# ble-jig-v1_1_-_respin.net
KiCad netlist of a schematic drawn in EAGLE
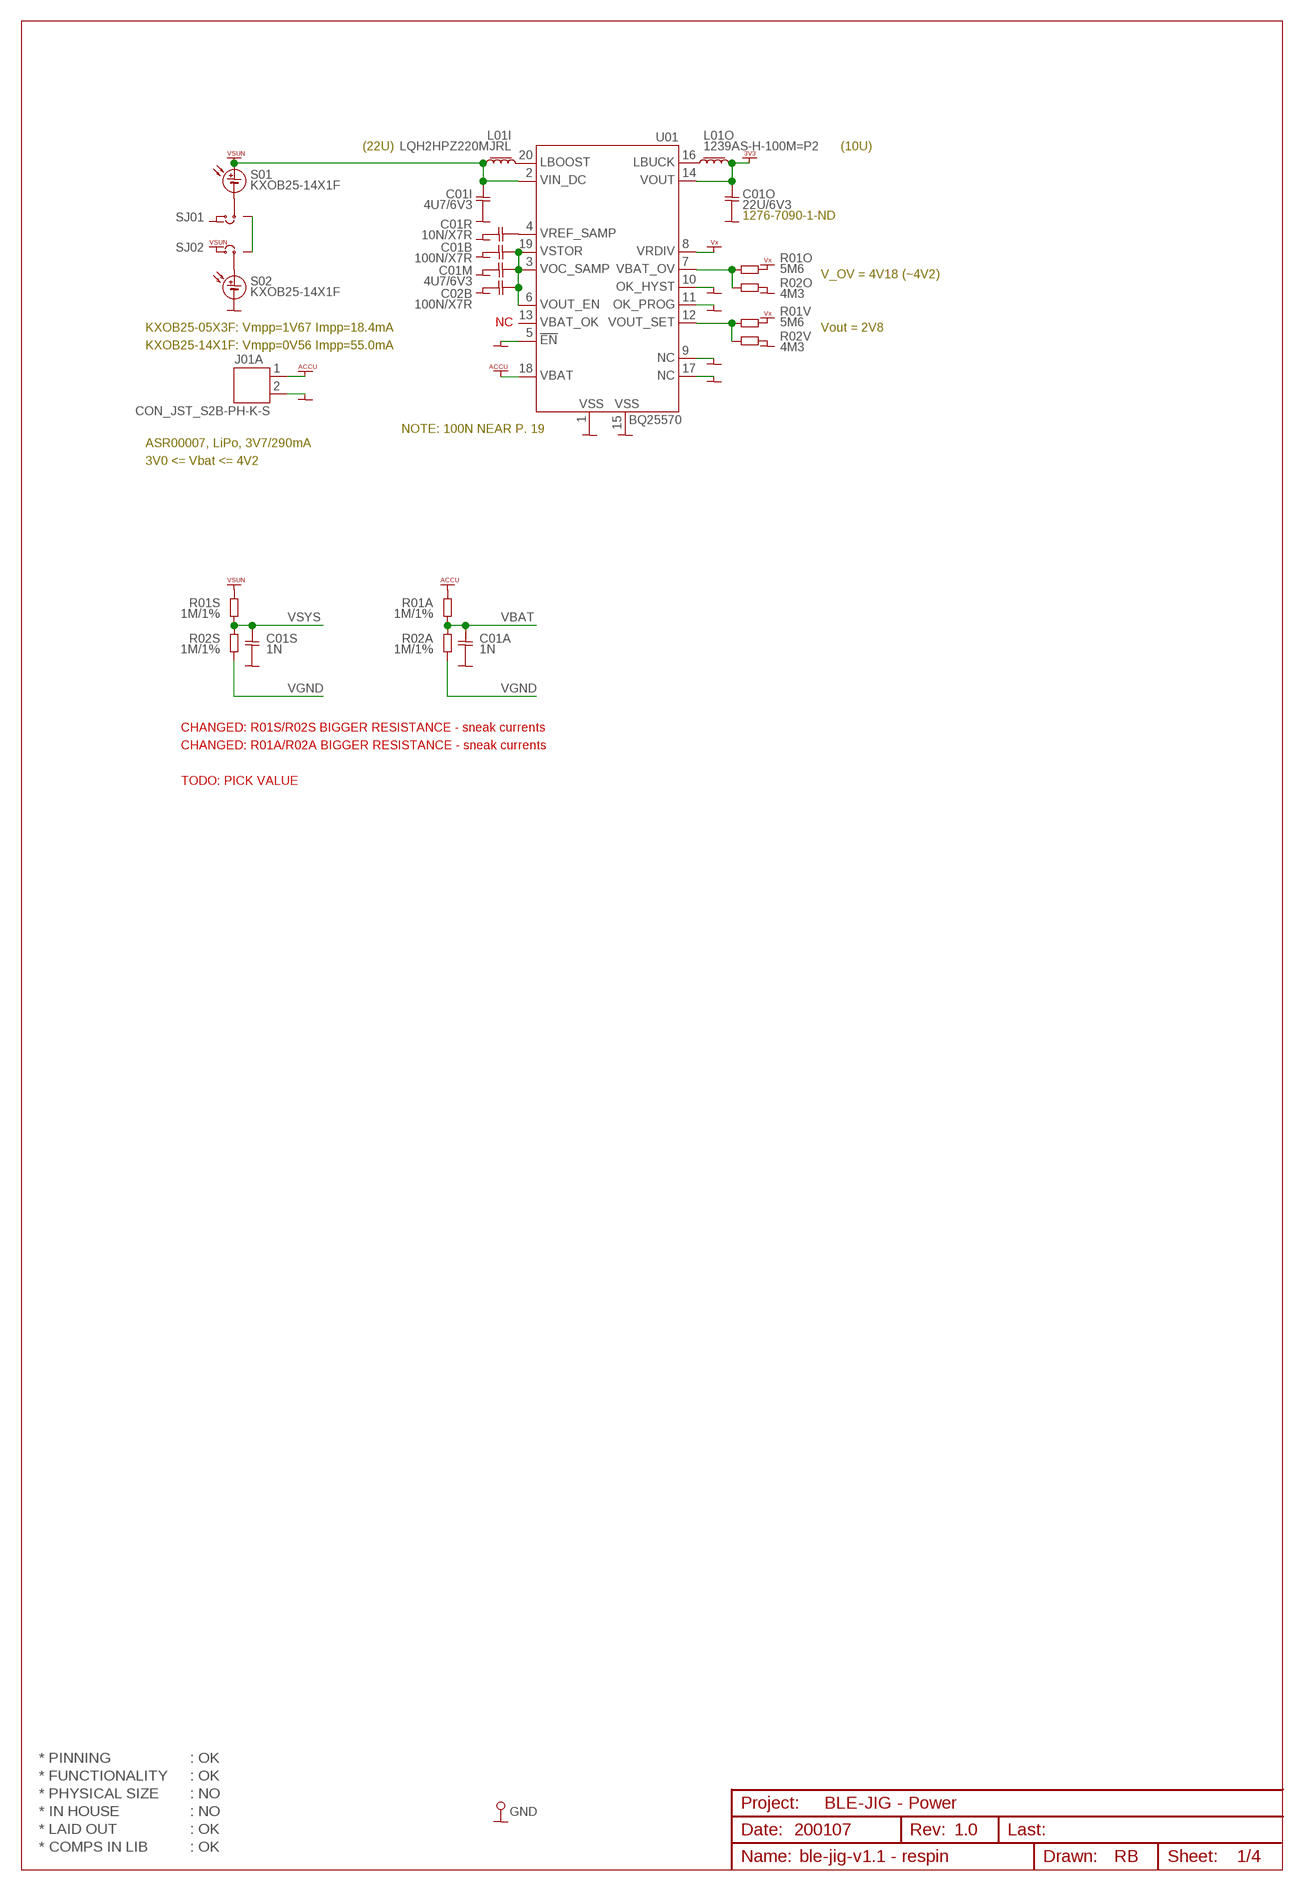
[diagram p0: schematic, sheet 1]
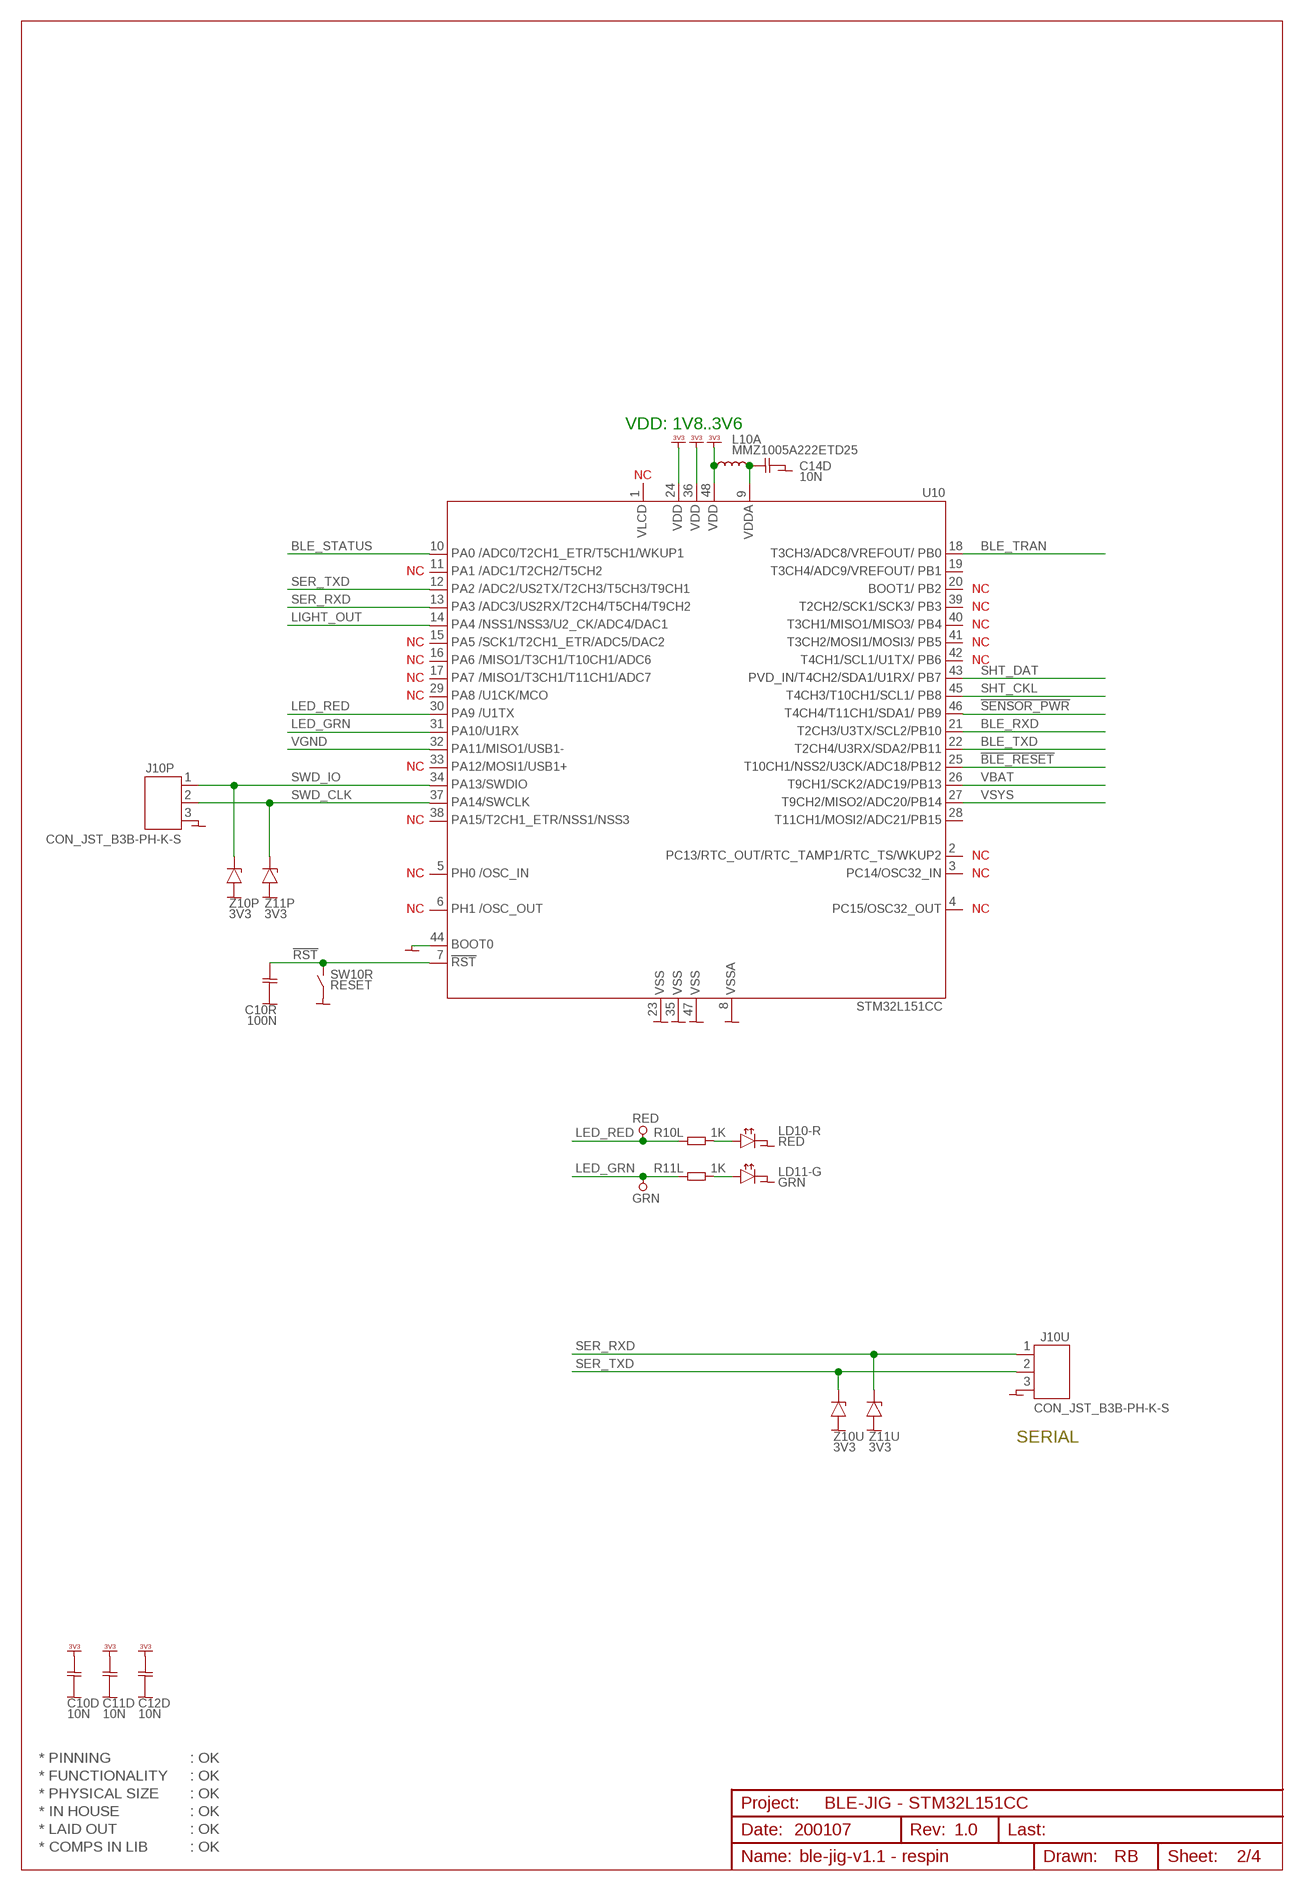
[diagram p1: schematic, sheet 2]
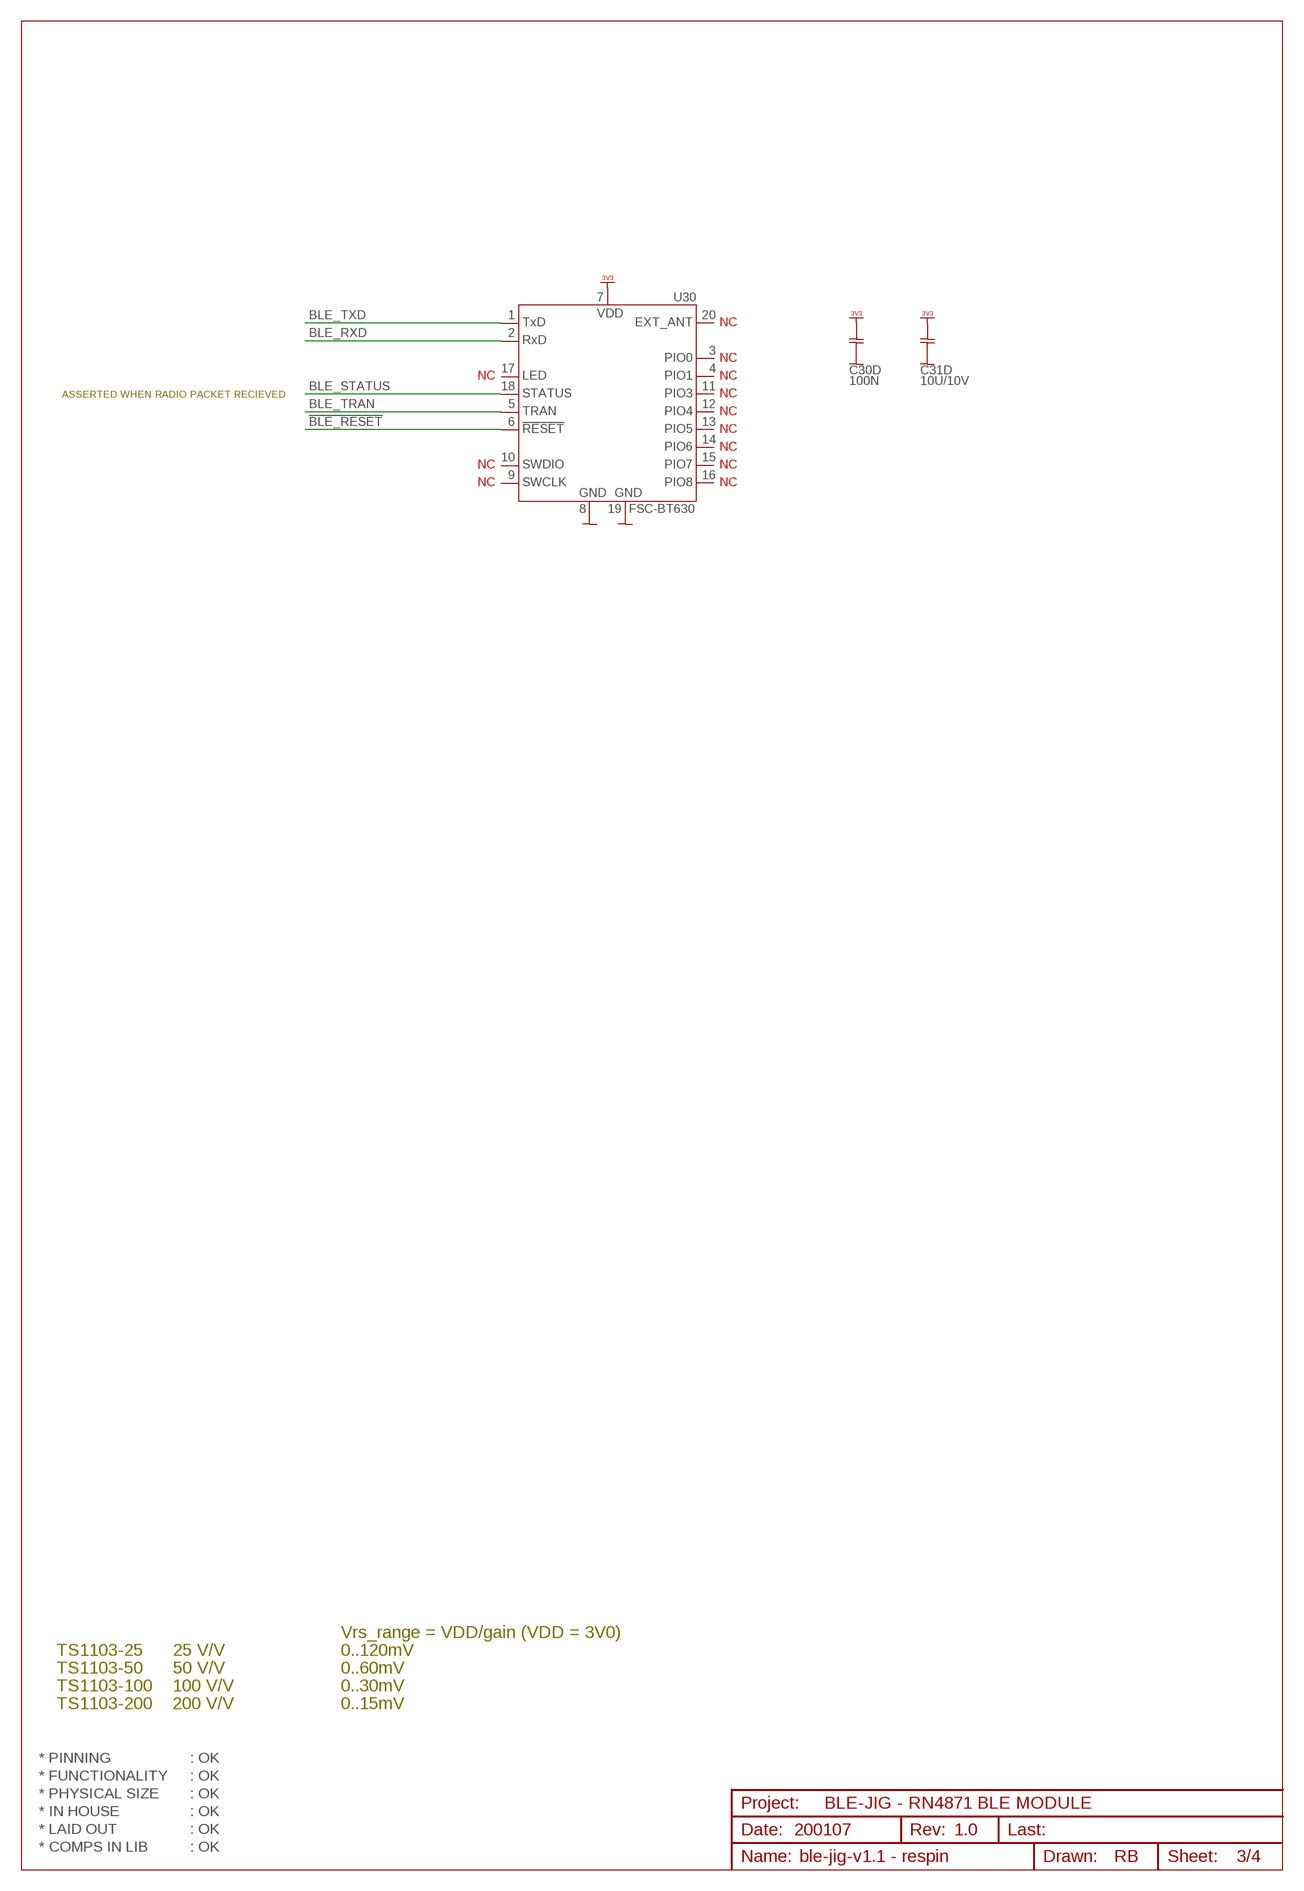
[diagram p2: schematic, sheet 3]
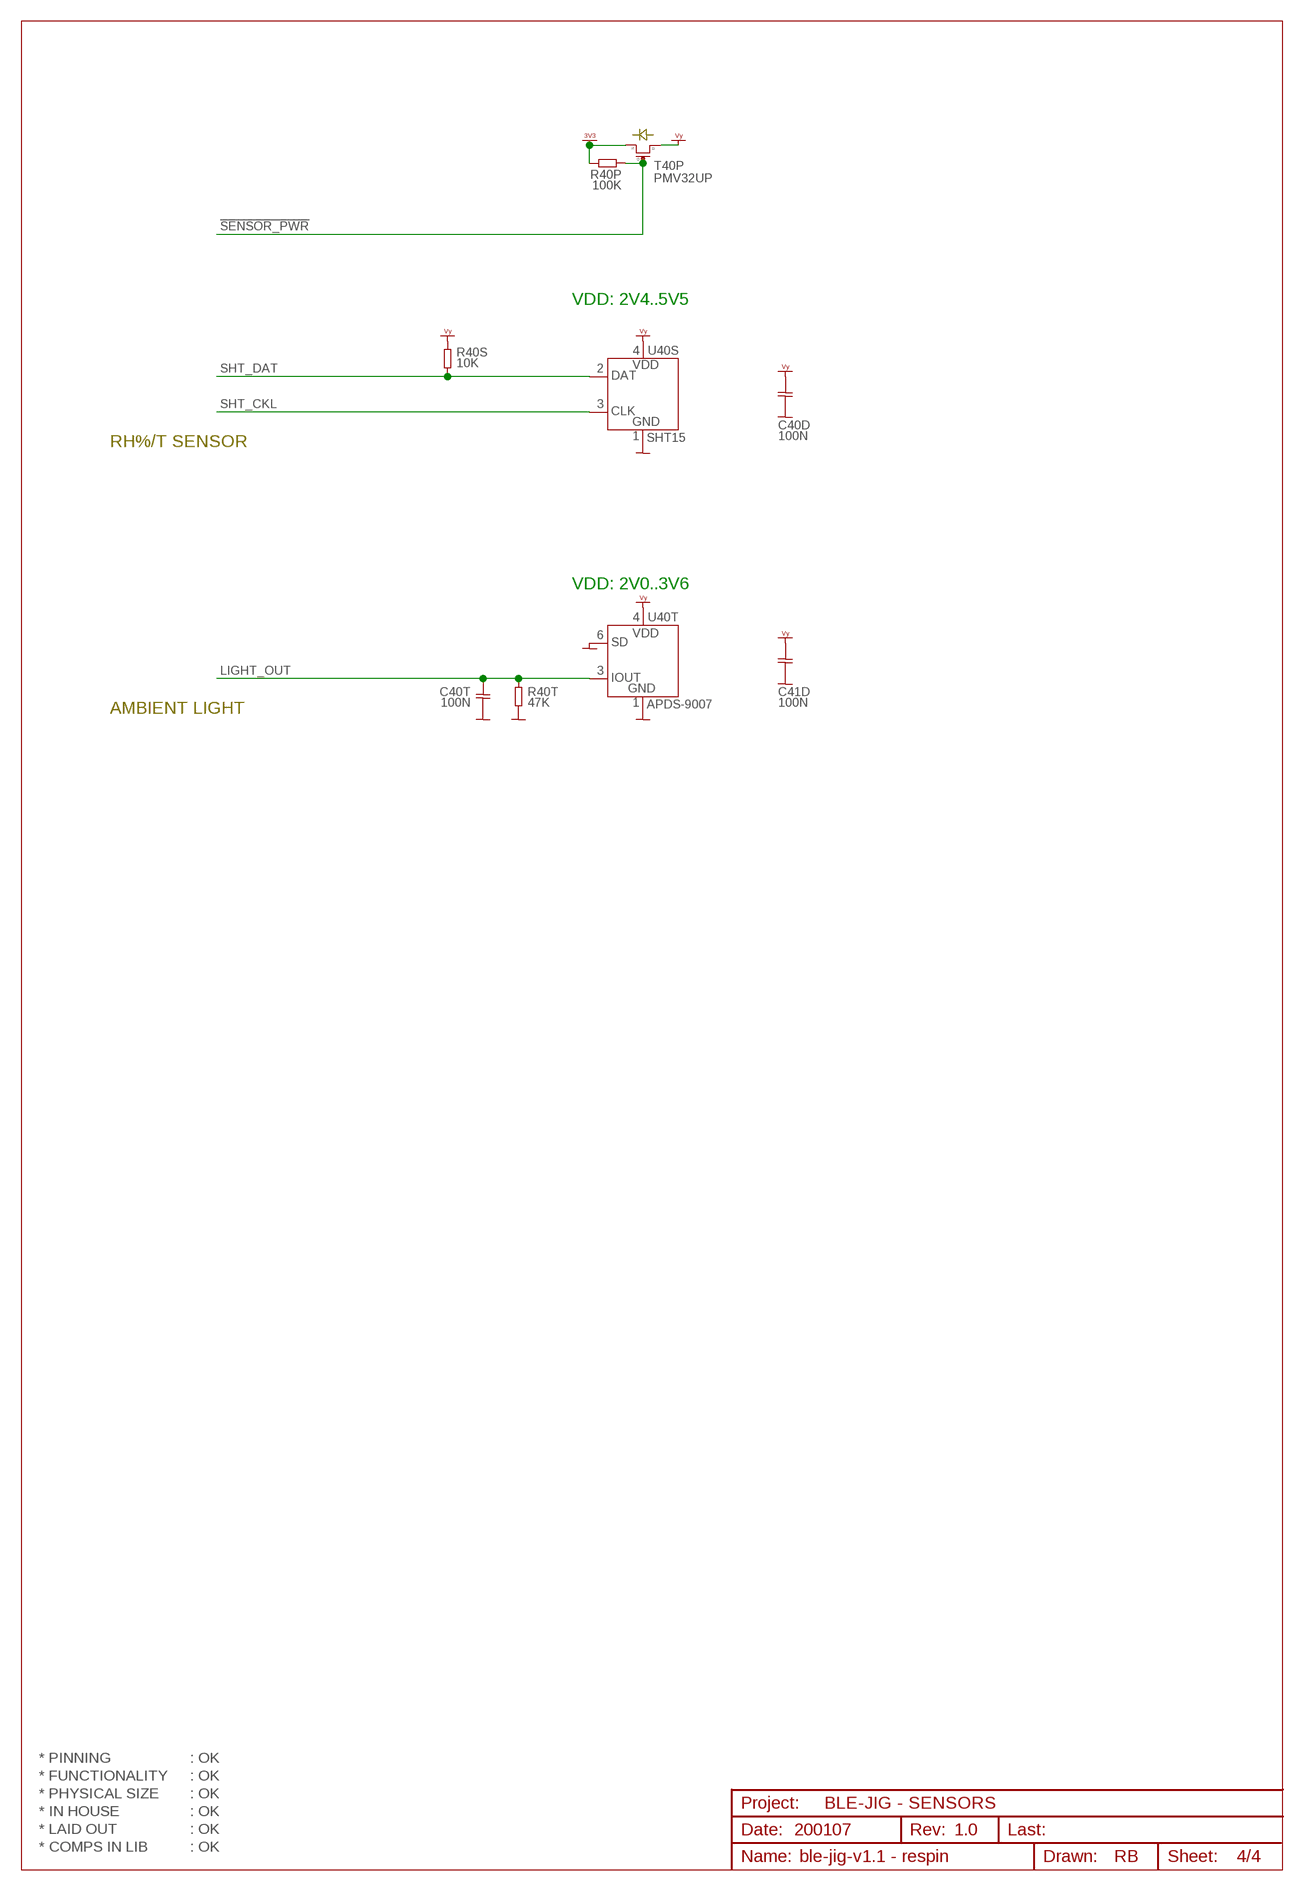
[diagram p3: schematic, sheet 4]

(export (version "E")
  (design (tool "Eeschema 10.0.6"))
  (components
    (comp (ref "C10D")
      (value "10N")
      (footprint "eagle-import:CAP0402")
      (libsource (lib "eagle-import") (part "CAP0402"))
    )
    (comp (ref "C10R")
      (value "100N")
      (footprint "eagle-import:CAP0402")
      (libsource (lib "eagle-import") (part "CAP0402"))
    )
    (comp (ref "C11D")
      (value "10N")
      (footprint "eagle-import:CAP0402")
      (libsource (lib "eagle-import") (part "CAP0402"))
    )
    (comp (ref "C12D")
      (value "10N")
      (footprint "eagle-import:CAP0402")
      (libsource (lib "eagle-import") (part "CAP0402"))
    )
    (comp (ref "C14D")
      (value "10N")
      (footprint "eagle-import:CAP0402")
      (libsource (lib "eagle-import") (part "CAP0402"))
    )
    (comp (ref "GRN")
      (value "PIN_TEST_0.6MM")
      (footprint "eagle-import:HOLE_PTH_0.6MM")
      (libsource (lib "eagle-import") (part "PIN_TEST_0.6MM"))
    )
    (comp (ref "J10P")
      (value "CON_JST_B3B-PH-K-S")
      (footprint "eagle-import:CON_JST_B3B-PH-K-S")
      (libsource (lib "eagle-import") (part "CON_JST_B3B-PH-K-S"))
    )
    (comp (ref "J10U")
      (value "CON_JST_B3B-PH-K-S")
      (footprint "eagle-import:CON_JST_B3B-PH-K-S")
      (libsource (lib "eagle-import") (part "CON_JST_B3B-PH-K-S"))
    )
    (comp (ref "L10A")
      (value "MMZ1005A222ETD25")
      (footprint "eagle-import:L_0402")
      (libsource (lib "eagle-import") (part "L_0402"))
    )
    (comp (ref "LD10-R")
      (value "RED")
      (footprint "eagle-import:LED_SMD_0402")
      (libsource (lib "eagle-import") (part "LED_SMD_0402"))
    )
    (comp (ref "LD11-G")
      (value "GRN")
      (footprint "eagle-import:LED_SMD_0402")
      (libsource (lib "eagle-import") (part "LED_SMD_0402"))
    )
    (comp (ref "R10L")
      (value "1K")
      (footprint "eagle-import:RES0402")
      (libsource (lib "eagle-import") (part "RES0402"))
    )
    (comp (ref "R11L")
      (value "1K")
      (footprint "eagle-import:RES0402")
      (libsource (lib "eagle-import") (part "RES0402"))
    )
    (comp (ref "RED")
      (value "PIN_TEST_0.6MM")
      (footprint "eagle-import:HOLE_PTH_0.6MM")
      (libsource (lib "eagle-import") (part "PIN_TEST_0.6MM"))
    )
    (comp (ref "SW10R")
      (value "RESET")
      (footprint "eagle-import:SWITCH_PUSHBUTTON_EVP-AVAA1A")
      (libsource (lib "eagle-import") (part "SWITCH_PUSHBUTTON_EVP-AVAA1A"))
    )
    (comp (ref "U10")
      (value "STM32L151CC")
      (footprint "eagle-import:LQFP48")
      (libsource (lib "eagle-import") (part "STM32L151CC"))
    )
    (comp (ref "Z10P")
      (value "3V3")
      (footprint "eagle-import:ZENER_SOD80")
      (libsource (lib "eagle-import") (part "ZENER_SOD80"))
    )
    (comp (ref "Z10U")
      (value "3V3")
      (footprint "eagle-import:ZENER_SOD80")
      (libsource (lib "eagle-import") (part "ZENER_SOD80"))
    )
    (comp (ref "Z11P")
      (value "3V3")
      (footprint "eagle-import:ZENER_SOD80")
      (libsource (lib "eagle-import") (part "ZENER_SOD80"))
    )
    (comp (ref "Z11U")
      (value "3V3")
      (footprint "eagle-import:ZENER_SOD80")
      (libsource (lib "eagle-import") (part "ZENER_SOD80"))
    )
    (comp (ref "C01A")
      (value "1N")
      (footprint "eagle-import:CAP0402")
      (libsource (lib "eagle-import") (part "CAP0402"))
    )
    (comp (ref "C01B")
      (value "100N/X7R")
      (footprint "eagle-import:CAP0402")
      (libsource (lib "eagle-import") (part "CAP0402"))
    )
    (comp (ref "C01I")
      (value "4U7/6V3")
      (footprint "eagle-import:CAP0402")
      (libsource (lib "eagle-import") (part "CAP0402"))
    )
    (comp (ref "C01M")
      (value "4U7/6V3")
      (footprint "eagle-import:CAP0402")
      (libsource (lib "eagle-import") (part "CAP0402"))
    )
    (comp (ref "C01O")
      (value "22U/6V3")
      (footprint "eagle-import:CAP0402")
      (libsource (lib "eagle-import") (part "CAP0402"))
    )
    (comp (ref "C01R")
      (value "10N/X7R")
      (footprint "eagle-import:CAP0402")
      (libsource (lib "eagle-import") (part "CAP0402"))
    )
    (comp (ref "C01S")
      (value "1N")
      (footprint "eagle-import:CAP0402")
      (libsource (lib "eagle-import") (part "CAP0402"))
    )
    (comp (ref "C02B")
      (value "100N/X7R")
      (footprint "eagle-import:CAP0402")
      (libsource (lib "eagle-import") (part "CAP0402"))
    )
    (comp (ref "GND")
      (value "PIN_TEST")
      (footprint "eagle-import:HOLE_PTH_0.8MM")
      (libsource (lib "eagle-import") (part "PIN_TEST"))
    )
    (comp (ref "J01A")
      (value "CON_JST_S2B-PH-K-S")
      (footprint "eagle-import:CON_JST_S2B-PH-K-S")
      (libsource (lib "eagle-import") (part "CON_JST_S2B-PH-K-S"))
    )
    (comp (ref "L01I")
      (value "LQH2HPZ220MJRL")
      (footprint "eagle-import:L_1008")
      (libsource (lib "eagle-import") (part "L_1008"))
    )
    (comp (ref "L01O")
      (value "1239AS-H-100M=P2")
      (footprint "eagle-import:L_1008")
      (libsource (lib "eagle-import") (part "L_1008"))
    )
    (comp (ref "R01A")
      (value "1M/1%")
      (footprint "eagle-import:RES0402")
      (libsource (lib "eagle-import") (part "RES0402"))
    )
    (comp (ref "R01O")
      (value "5M6")
      (footprint "eagle-import:RES0402")
      (libsource (lib "eagle-import") (part "RES0402"))
    )
    (comp (ref "R01S")
      (value "1M/1%")
      (footprint "eagle-import:RES0402")
      (libsource (lib "eagle-import") (part "RES0402"))
    )
    (comp (ref "R01V")
      (value "5M6")
      (footprint "eagle-import:RES0402")
      (libsource (lib "eagle-import") (part "RES0402"))
    )
    (comp (ref "R02A")
      (value "1M/1%")
      (footprint "eagle-import:RES0402")
      (libsource (lib "eagle-import") (part "RES0402"))
    )
    (comp (ref "R02O")
      (value "4M3")
      (footprint "eagle-import:RES0402")
      (libsource (lib "eagle-import") (part "RES0402"))
    )
    (comp (ref "R02S")
      (value "1M/1%")
      (footprint "eagle-import:RES0402")
      (libsource (lib "eagle-import") (part "RES0402"))
    )
    (comp (ref "R02V")
      (value "4M3")
      (footprint "eagle-import:RES0402")
      (libsource (lib "eagle-import") (part "RES0402"))
    )
    (comp (ref "S01")
      (value "KXOB25-14X1F")
      (footprint "eagle-import:KXOB25-14X1F")
      (libsource (lib "eagle-import") (part "KXOB25-14X1F"))
    )
    (comp (ref "S02")
      (value "KXOB25-14X1F")
      (footprint "eagle-import:KXOB25-14X1F")
      (libsource (lib "eagle-import") (part "KXOB25-14X1F"))
    )
    (comp (ref "SJ01")
      (value "SJ3SJ3-S")
      (footprint "eagle-import:SJ3-S")
      (libsource (lib "eagle-import") (part "SJ3SJ3-S"))
    )
    (comp (ref "SJ02")
      (value "SJ3SJ3-S")
      (footprint "eagle-import:SJ3-S")
      (libsource (lib "eagle-import") (part "SJ3SJ3-S"))
    )
    (comp (ref "U01")
      (value "BQ25570")
      (footprint "eagle-import:VQFN20")
      (libsource (lib "eagle-import") (part "BQ25570"))
    )
    (comp (ref "C30D")
      (value "100N")
      (footprint "eagle-import:CAP0402")
      (libsource (lib "eagle-import") (part "CAP0402"))
    )
    (comp (ref "C31D")
      (value "10U/10V")
      (footprint "eagle-import:CAP0402")
      (libsource (lib "eagle-import") (part "CAP0402"))
    )
    (comp (ref "U30")
      (value "FSC-BT630")
      (footprint "eagle-import:FSC-BT630")
      (libsource (lib "eagle-import") (part "FSC-BT630"))
    )
    (comp (ref "C40D")
      (value "100N")
      (footprint "eagle-import:CAP0402")
      (libsource (lib "eagle-import") (part "CAP0402"))
    )
    (comp (ref "C40T")
      (value "100N")
      (footprint "eagle-import:CAP0402")
      (libsource (lib "eagle-import") (part "CAP0402"))
    )
    (comp (ref "C41D")
      (value "100N")
      (footprint "eagle-import:CAP0402")
      (libsource (lib "eagle-import") (part "CAP0402"))
    )
    (comp (ref "R40P")
      (value "100K")
      (footprint "eagle-import:RES0402")
      (libsource (lib "eagle-import") (part "RES0402"))
    )
    (comp (ref "R40S")
      (value "10K")
      (footprint "eagle-import:RES0402")
      (libsource (lib "eagle-import") (part "RES0402"))
    )
    (comp (ref "R40T")
      (value "47K")
      (footprint "eagle-import:RES0402")
      (libsource (lib "eagle-import") (part "RES0402"))
    )
    (comp (ref "T40P")
      (value "PMV32UP")
      (footprint "eagle-import:PFET_SOT23")
      (libsource (lib "eagle-import") (part "PFET_SOT23"))
    )
    (comp (ref "U40S")
      (value "SHT15")
      (footprint "eagle-import:SHT15")
      (libsource (lib "eagle-import") (part "SHT15"))
    )
    (comp (ref "U40T")
      (value "APDS-9007")
      (footprint "eagle-import:APDS-9007")
      (libsource (lib "eagle-import") (part "APDS-9007"))
    )
  )
  (nets
    (net (code "1") (name "ACCU") (class "Default")
      (node (ref "J01A") (pin "1") (pinfunction "1_1") (pintype "passive"))
      (node (ref "R01A") (pin "2") (pinfunction "2_2") (pintype "passive"))
      (node (ref "U01") (pin "18") (pinfunction "18.VBAT_18") (pintype "passive"))
    )
    (net (code "2") (name "BLE_RXD") (class "Default")
      (node (ref "U10") (pin "21") (pinfunction "21.PB10_21") (pintype "passive"))
      (node (ref "U30") (pin "2") (pinfunction "2.RXD_2") (pintype "passive"))
    )
    (net (code "3") (name "BLE_STATUS") (class "Default")
      (node (ref "U10") (pin "10") (pinfunction "10.PA0_10") (pintype "passive"))
      (node (ref "U30") (pin "18") (pinfunction "18.STATUS_18") (pintype "passive"))
    )
    (net (code "4") (name "BLE_TRAN") (class "Default")
      (node (ref "U10") (pin "18") (pinfunction "18.PB0_18") (pintype "passive"))
      (node (ref "U30") (pin "5") (pinfunction "5.TRAN_5") (pintype "passive"))
    )
    (net (code "5") (name "BLE_TXD") (class "Default")
      (node (ref "U10") (pin "22") (pinfunction "22.PB11_22") (pintype "passive"))
      (node (ref "U30") (pin "1") (pinfunction "1.TXD_1") (pintype "passive"))
    )
    (net (code "6") (name "GND") (class "Default")
      (node (ref "C01A") (pin "2") (pinfunction "2_2") (pintype "passive"))
      (node (ref "C01B") (pin "2") (pinfunction "2_2") (pintype "passive"))
      (node (ref "C01I") (pin "2") (pinfunction "2_2") (pintype "passive"))
      (node (ref "C01M") (pin "2") (pinfunction "2_2") (pintype "passive"))
      (node (ref "C01O") (pin "2") (pinfunction "2_2") (pintype "passive"))
      (node (ref "C01R") (pin "2") (pinfunction "2_2") (pintype "passive"))
      (node (ref "C01S") (pin "2") (pinfunction "2_2") (pintype "passive"))
      (node (ref "C02B") (pin "2") (pinfunction "2_2") (pintype "passive"))
      (node (ref "C10D") (pin "2") (pinfunction "2_2") (pintype "passive"))
      (node (ref "C10R") (pin "2") (pinfunction "2_2") (pintype "passive"))
      (node (ref "C11D") (pin "2") (pinfunction "2_2") (pintype "passive"))
      (node (ref "C12D") (pin "2") (pinfunction "2_2") (pintype "passive"))
      (node (ref "C14D") (pin "2") (pinfunction "2_2") (pintype "passive"))
      (node (ref "C30D") (pin "2") (pinfunction "2_2") (pintype "passive"))
      (node (ref "C31D") (pin "2") (pinfunction "2_2") (pintype "passive"))
      (node (ref "C40D") (pin "2") (pinfunction "2_2") (pintype "passive"))
      (node (ref "C40T") (pin "2") (pinfunction "2_2") (pintype "passive"))
      (node (ref "C41D") (pin "2") (pinfunction "2_2") (pintype "passive"))
      (node (ref "GND") (pin "1") (pinfunction "P$1_1") (pintype "passive"))
      (node (ref "J01A") (pin "2") (pinfunction "2_2") (pintype "passive"))
      (node (ref "J10P") (pin "3") (pinfunction "3_3") (pintype "passive"))
      (node (ref "J10U") (pin "3") (pinfunction "3_3") (pintype "passive"))
      (node (ref "LD10-R") (pin "C") (pinfunction "C_C") (pintype "passive"))
      (node (ref "LD11-G") (pin "C") (pinfunction "C_C") (pintype "passive"))
      (node (ref "R02O") (pin "2") (pinfunction "2_2") (pintype "passive"))
      (node (ref "R02V") (pin "2") (pinfunction "2_2") (pintype "passive"))
      (node (ref "R40T") (pin "2") (pinfunction "2_2") (pintype "passive"))
      (node (ref "S02") (pin "2") (pinfunction "2_2") (pintype "passive"))
      (node (ref "SJ01") (pin "1") (pinfunction "1_1") (pintype "passive"))
      (node (ref "SW10R") (pin "2") (pinfunction "3-4_2") (pintype "passive"))
      (node (ref "U01") (pin "1") (pinfunction "1.VSS_1") (pintype "passive"))
      (node (ref "U01") (pin "10") (pinfunction "10.OK_HYST_10") (pintype "passive"))
      (node (ref "U01") (pin "11") (pinfunction "11.OK_PROG_11") (pintype "passive"))
      (node (ref "U01") (pin "15") (pinfunction "15.VSS_15") (pintype "passive"))
      (node (ref "U01") (pin "17") (pinfunction "17.NC_17") (pintype "passive"))
      (node (ref "U01") (pin "5") (pinfunction "5.~{EN}_5") (pintype "passive"))
      (node (ref "U01") (pin "9") (pinfunction "9.NC_9") (pintype "passive"))
      (node (ref "U01") (pin "TP") (pinfunction "15.VSS_TP") (pintype "passive"))
      (node (ref "U01") (pin "V1") (pinfunction "15.VSS_V1") (pintype "passive"))
      (node (ref "U01") (pin "V2") (pinfunction "15.VSS_V2") (pintype "passive"))
      (node (ref "U01") (pin "V3") (pinfunction "15.VSS_V3") (pintype "passive"))
      (node (ref "U01") (pin "V4") (pinfunction "15.VSS_V4") (pintype "passive"))
      (node (ref "U10") (pin "23") (pinfunction "23.GND_23") (pintype "passive"))
      (node (ref "U10") (pin "35") (pinfunction "35.GND_35") (pintype "passive"))
      (node (ref "U10") (pin "44") (pinfunction "44.BOOT0_44") (pintype "passive"))
      (node (ref "U10") (pin "47") (pinfunction "47.GND_47") (pintype "passive"))
      (node (ref "U10") (pin "8") (pinfunction "8.GND_8") (pintype "passive"))
      (node (ref "U30") (pin "19") (pinfunction "19.GND_19") (pintype "passive"))
      (node (ref "U30") (pin "8") (pinfunction "8.GND_8") (pintype "passive"))
      (node (ref "U40S") (pin "1") (pinfunction "1.GND_1") (pintype "passive"))
      (node (ref "U40T") (pin "1") (pinfunction "1.GND_1") (pintype "passive"))
      (node (ref "U40T") (pin "6") (pinfunction "6.SD_6") (pintype "passive"))
      (node (ref "Z10P") (pin "1") (pinfunction "A_1") (pintype "passive"))
      (node (ref "Z10U") (pin "1") (pinfunction "A_1") (pintype "passive"))
      (node (ref "Z11P") (pin "1") (pinfunction "A_1") (pintype "passive"))
      (node (ref "Z11U") (pin "1") (pinfunction "A_1") (pintype "passive"))
    )
    (net (code "7") (name "LED_GRN") (class "Default")
      (node (ref "GRN") (pin "1") (pinfunction "P$1_1") (pintype "passive"))
      (node (ref "R11L") (pin "1") (pinfunction "1_1") (pintype "passive"))
      (node (ref "U10") (pin "31") (pinfunction "31.PA10_31") (pintype "passive"))
    )
    (net (code "8") (name "LED_RED") (class "Default")
      (node (ref "R10L") (pin "1") (pinfunction "1_1") (pintype "passive"))
      (node (ref "RED") (pin "1") (pinfunction "P$1_1") (pintype "passive"))
      (node (ref "U10") (pin "30") (pinfunction "30.PA9_30") (pintype "passive"))
    )
    (net (code "9") (name "LIGHT_OUT") (class "Default")
      (node (ref "C40T") (pin "1") (pinfunction "1_1") (pintype "passive"))
      (node (ref "R40T") (pin "1") (pinfunction "1_1") (pintype "passive"))
      (node (ref "U10") (pin "14") (pinfunction "14.PA4_14") (pintype "passive"))
      (node (ref "U40T") (pin "3") (pinfunction "3.IOUT_3") (pintype "passive"))
    )
    (net (code "10") (name "Net-(LD10-R-PadA)") (class "Default")
      (node (ref "LD10-R") (pin "A") (pinfunction "A_A") (pintype "passive"))
      (node (ref "R10L") (pin "2") (pinfunction "2_2") (pintype "passive"))
    )
    (net (code "11") (name "Net-(LD11-G-PadA)") (class "Default")
      (node (ref "LD11-G") (pin "A") (pinfunction "A_A") (pintype "passive"))
      (node (ref "R11L") (pin "2") (pinfunction "2_2") (pintype "passive"))
    )
    (net (code "12") (name "Net-(S01-Pad2)") (class "Default")
      (node (ref "S01") (pin "2") (pinfunction "2_2") (pintype "passive"))
      (node (ref "SJ01") (pin "2") (pinfunction "2_2") (pintype "passive"))
    )
    (net (code "13") (name "Net-(S02-Pad1)") (class "Default")
      (node (ref "S02") (pin "1") (pinfunction "1_1") (pintype "passive"))
      (node (ref "SJ02") (pin "2") (pinfunction "2_2") (pintype "passive"))
    )
    (net (code "14") (name "Net-(SJ01-Pad3)") (class "Default")
      (node (ref "SJ01") (pin "3") (pinfunction "3_3") (pintype "passive"))
      (node (ref "SJ02") (pin "3") (pinfunction "3_3") (pintype "passive"))
    )
    (net (code "15") (name "Net-(U01-4.VREF_SAMP)") (class "Default")
      (node (ref "C01R") (pin "1") (pinfunction "1_1") (pintype "passive"))
      (node (ref "U01") (pin "4") (pinfunction "4.VREF_SAMP_4") (pintype "passive"))
    )
    (net (code "16") (name "Net-(U01-7.VBAT_OV)") (class "Default")
      (node (ref "R01O") (pin "2") (pinfunction "2_2") (pintype "passive"))
      (node (ref "R02O") (pin "1") (pinfunction "1_1") (pintype "passive"))
      (node (ref "U01") (pin "7") (pinfunction "7.VBAT_OV_7") (pintype "passive"))
    )
    (net (code "17") (name "Net-(U01-12.VOUT_SET)") (class "Default")
      (node (ref "R01V") (pin "2") (pinfunction "2_2") (pintype "passive"))
      (node (ref "R02V") (pin "1") (pinfunction "1_1") (pintype "passive"))
      (node (ref "U01") (pin "12") (pinfunction "12.VOUT_SET_12") (pintype "passive"))
    )
    (net (code "18") (name "Net-(U01-16.LBUCK)") (class "Default")
      (node (ref "L01O") (pin "1") (pinfunction "1_1") (pintype "passive"))
      (node (ref "U01") (pin "16") (pinfunction "16.LBUCK_16") (pintype "passive"))
    )
    (net (code "19") (name "Net-(U01-19.VSTOR)") (class "Default")
      (node (ref "C01B") (pin "1") (pinfunction "1_1") (pintype "passive"))
      (node (ref "C01M") (pin "1") (pinfunction "1_1") (pintype "passive"))
      (node (ref "C02B") (pin "1") (pinfunction "1_1") (pintype "passive"))
      (node (ref "U01") (pin "19") (pinfunction "19.VSTOR_19") (pintype "passive"))
      (node (ref "U01") (pin "3") (pinfunction "3.VOC_SAMP_3") (pintype "passive"))
      (node (ref "U01") (pin "6") (pinfunction "6.VOUT_EN_6") (pintype "passive"))
    )
    (net (code "20") (name "Net-(U01-20.LBOOST)") (class "Default")
      (node (ref "L01I") (pin "2") (pinfunction "2_2") (pintype "passive"))
      (node (ref "U01") (pin "20") (pinfunction "20.LBOOST_20") (pintype "passive"))
    )
    (net (code "21") (name "Net-(U10-9.VDD)") (class "Default")
      (node (ref "C14D") (pin "1") (pinfunction "1_1") (pintype "passive"))
      (node (ref "L10A") (pin "2") (pinfunction "2_2") (pintype "passive"))
      (node (ref "U10") (pin "9") (pinfunction "9.VDD_9") (pintype "passive"))
    )
    (net (code "22") (name "SER_RXD") (class "Default")
      (node (ref "J10U") (pin "1") (pinfunction "1_1") (pintype "passive"))
      (node (ref "U10") (pin "13") (pinfunction "13.PA3_13") (pintype "passive"))
      (node (ref "Z11U") (pin "2") (pinfunction "C_2") (pintype "passive"))
    )
    (net (code "23") (name "SER_TXD") (class "Default")
      (node (ref "J10U") (pin "2") (pinfunction "2_2") (pintype "passive"))
      (node (ref "U10") (pin "12") (pinfunction "12.PA2_12") (pintype "passive"))
      (node (ref "Z10U") (pin "2") (pinfunction "C_2") (pintype "passive"))
    )
    (net (code "24") (name "SHT_CKL") (class "Default")
      (node (ref "U10") (pin "45") (pinfunction "45.PB8_45") (pintype "passive"))
      (node (ref "U40S") (pin "3") (pinfunction "3.CLK_3") (pintype "passive"))
    )
    (net (code "25") (name "SHT_DAT") (class "Default")
      (node (ref "R40S") (pin "2") (pinfunction "2_2") (pintype "passive"))
      (node (ref "U10") (pin "43") (pinfunction "43.PB7_43") (pintype "passive"))
      (node (ref "U40S") (pin "2") (pinfunction "2.DAT_2") (pintype "passive"))
    )
    (net (code "26") (name "SWD_CLK") (class "Default")
      (node (ref "J10P") (pin "2") (pinfunction "2_2") (pintype "passive"))
      (node (ref "U10") (pin "37") (pinfunction "37.PA14_37") (pintype "passive"))
      (node (ref "Z11P") (pin "2") (pinfunction "C_2") (pintype "passive"))
    )
    (net (code "27") (name "SWD_IO") (class "Default")
      (node (ref "J10P") (pin "1") (pinfunction "1_1") (pintype "passive"))
      (node (ref "U10") (pin "34") (pinfunction "34.PA13_34") (pintype "passive"))
      (node (ref "Z10P") (pin "2") (pinfunction "C_2") (pintype "passive"))
    )
    (net (code "28") (name "VBAT") (class "Default")
      (node (ref "C01A") (pin "1") (pinfunction "1_1") (pintype "passive"))
      (node (ref "R01A") (pin "1") (pinfunction "1_1") (pintype "passive"))
      (node (ref "R02A") (pin "2") (pinfunction "2_2") (pintype "passive"))
      (node (ref "U10") (pin "26") (pinfunction "26.PB13_26") (pintype "passive"))
    )
    (net (code "29") (name "VDD_3V3") (class "Default")
      (node (ref "C01O") (pin "1") (pinfunction "1_1") (pintype "passive"))
      (node (ref "C10D") (pin "1") (pinfunction "1_1") (pintype "passive"))
      (node (ref "C11D") (pin "1") (pinfunction "1_1") (pintype "passive"))
      (node (ref "C12D") (pin "1") (pinfunction "1_1") (pintype "passive"))
      (node (ref "C30D") (pin "1") (pinfunction "1_1") (pintype "passive"))
      (node (ref "C31D") (pin "1") (pinfunction "1_1") (pintype "passive"))
      (node (ref "L01O") (pin "2") (pinfunction "2_2") (pintype "passive"))
      (node (ref "L10A") (pin "1") (pinfunction "1_1") (pintype "passive"))
      (node (ref "R40P") (pin "1") (pinfunction "1_1") (pintype "passive"))
      (node (ref "T40P") (pin "2") (pinfunction "S_2") (pintype "bidirectional"))
      (node (ref "U01") (pin "14") (pinfunction "14.VOUT_14") (pintype "passive"))
      (node (ref "U10") (pin "24") (pinfunction "24.VDD_24") (pintype "passive"))
      (node (ref "U10") (pin "36") (pinfunction "36.VDD_36") (pintype "passive"))
      (node (ref "U10") (pin "48") (pinfunction "48.VDD_48") (pintype "passive"))
      (node (ref "U30") (pin "7") (pinfunction "7.VDD_7") (pintype "passive"))
    )
    (net (code "30") (name "VGND") (class "Default")
      (node (ref "R02A") (pin "1") (pinfunction "1_1") (pintype "passive"))
      (node (ref "R02S") (pin "1") (pinfunction "1_1") (pintype "passive"))
      (node (ref "U10") (pin "32") (pinfunction "32.PA11_32") (pintype "passive"))
    )
    (net (code "31") (name "VSUN") (class "Default")
      (node (ref "C01I") (pin "1") (pinfunction "1_1") (pintype "passive"))
      (node (ref "L01I") (pin "1") (pinfunction "1_1") (pintype "passive"))
      (node (ref "R01S") (pin "2") (pinfunction "2_2") (pintype "passive"))
      (node (ref "S01") (pin "1") (pinfunction "1_1") (pintype "passive"))
      (node (ref "SJ02") (pin "1") (pinfunction "1_1") (pintype "passive"))
      (node (ref "U01") (pin "2") (pinfunction "2.VIN_DC_2") (pintype "passive"))
    )
    (net (code "32") (name "VSYS") (class "Default")
      (node (ref "C01S") (pin "1") (pinfunction "1_1") (pintype "passive"))
      (node (ref "R01S") (pin "1") (pinfunction "1_1") (pintype "passive"))
      (node (ref "R02S") (pin "2") (pinfunction "2_2") (pintype "passive"))
      (node (ref "U10") (pin "27") (pinfunction "27.PB14_27") (pintype "passive"))
    )
    (net (code "33") (name "VX") (class "Default")
      (node (ref "R01O") (pin "1") (pinfunction "1_1") (pintype "passive"))
      (node (ref "R01V") (pin "1") (pinfunction "1_1") (pintype "passive"))
      (node (ref "U01") (pin "8") (pinfunction "8.VRDIV_8") (pintype "passive"))
    )
    (net (code "34") (name "VY") (class "Default")
      (node (ref "C40D") (pin "1") (pinfunction "1_1") (pintype "passive"))
      (node (ref "C41D") (pin "1") (pinfunction "1_1") (pintype "passive"))
      (node (ref "R40S") (pin "1") (pinfunction "1_1") (pintype "passive"))
      (node (ref "T40P") (pin "3") (pinfunction "D_3") (pintype "bidirectional"))
      (node (ref "U40S") (pin "4") (pinfunction "4.VDD_4") (pintype "passive"))
      (node (ref "U40T") (pin "4") (pinfunction "4.VDD_4") (pintype "passive"))
    )
    (net (code "35") (name "unconnected-(U01-13.VBAT_OK-Pad13)") (class "Default")
      (node (ref "U01") (pin "13") (pinfunction "13.VBAT_OK_13") (pintype "passive"))
    )
    (net (code "36") (name "unconnected-(U10-1.VDD-Pad1)") (class "Default")
      (node (ref "U10") (pin "1") (pinfunction "1.VDD_1") (pintype "passive"))
    )
    (net (code "37") (name "unconnected-(U10-2.PC13-Pad2)") (class "Default")
      (node (ref "U10") (pin "2") (pinfunction "2.PC13_2") (pintype "passive"))
    )
    (net (code "38") (name "unconnected-(U10-3.PC14-Pad3)") (class "Default")
      (node (ref "U10") (pin "3") (pinfunction "3.PC14_3") (pintype "passive"))
    )
    (net (code "39") (name "unconnected-(U10-4.PC15-Pad4)") (class "Default")
      (node (ref "U10") (pin "4") (pinfunction "4.PC15_4") (pintype "passive"))
    )
    (net (code "40") (name "unconnected-(U10-5.OSC_IN-Pad5)") (class "Default")
      (node (ref "U10") (pin "5") (pinfunction "5.OSC_IN_5") (pintype "passive"))
    )
    (net (code "41") (name "unconnected-(U10-6.OSC_OUT-Pad6)") (class "Default")
      (node (ref "U10") (pin "6") (pinfunction "6.OSC_OUT_6") (pintype "passive"))
    )
    (net (code "42") (name "unconnected-(U10-11.PA1-Pad11)") (class "Default")
      (node (ref "U10") (pin "11") (pinfunction "11.PA1_11") (pintype "passive"))
    )
    (net (code "43") (name "unconnected-(U10-15.PA5-Pad15)") (class "Default")
      (node (ref "U10") (pin "15") (pinfunction "15.PA5_15") (pintype "passive"))
    )
    (net (code "44") (name "unconnected-(U10-16.PA6-Pad16)") (class "Default")
      (node (ref "U10") (pin "16") (pinfunction "16.PA6_16") (pintype "passive"))
    )
    (net (code "45") (name "unconnected-(U10-17.PA7-Pad17)") (class "Default")
      (node (ref "U10") (pin "17") (pinfunction "17.PA7_17") (pintype "passive"))
    )
    (net (code "46") (name "unconnected-(U10-19.PB1-Pad19)") (class "Default")
      (node (ref "U10") (pin "19") (pinfunction "19.PB1_19") (pintype "passive"))
    )
    (net (code "47") (name "unconnected-(U10-20.PB2-Pad20)") (class "Default")
      (node (ref "U10") (pin "20") (pinfunction "20.PB2_20") (pintype "passive"))
    )
    (net (code "48") (name "unconnected-(U10-28.PB15-Pad28)") (class "Default")
      (node (ref "U10") (pin "28") (pinfunction "28.PB15_28") (pintype "passive"))
    )
    (net (code "49") (name "unconnected-(U10-29.PA8-Pad29)") (class "Default")
      (node (ref "U10") (pin "29") (pinfunction "29.PA8_29") (pintype "passive"))
    )
    (net (code "50") (name "unconnected-(U10-33.PA12-Pad33)") (class "Default")
      (node (ref "U10") (pin "33") (pinfunction "33.PA12_33") (pintype "passive"))
    )
    (net (code "51") (name "unconnected-(U10-38.PA15-Pad38)") (class "Default")
      (node (ref "U10") (pin "38") (pinfunction "38.PA15_38") (pintype "passive"))
    )
    (net (code "52") (name "unconnected-(U10-39.PB3-Pad39)") (class "Default")
      (node (ref "U10") (pin "39") (pinfunction "39.PB3_39") (pintype "passive"))
    )
    (net (code "53") (name "unconnected-(U10-40.PB4-Pad40)") (class "Default")
      (node (ref "U10") (pin "40") (pinfunction "40.PB4_40") (pintype "passive"))
    )
    (net (code "54") (name "unconnected-(U10-41.PB5-Pad41)") (class "Default")
      (node (ref "U10") (pin "41") (pinfunction "41.PB5_41") (pintype "passive"))
    )
    (net (code "55") (name "unconnected-(U10-42.PB6-Pad42)") (class "Default")
      (node (ref "U10") (pin "42") (pinfunction "42.PB6_42") (pintype "passive"))
    )
    (net (code "56") (name "unconnected-(U30-3.PIO0-Pad3)") (class "Default")
      (node (ref "U30") (pin "3") (pinfunction "3.PIO0_3") (pintype "passive"))
    )
    (net (code "57") (name "unconnected-(U30-4.PIO1-Pad4)") (class "Default")
      (node (ref "U30") (pin "4") (pinfunction "4.PIO1_4") (pintype "passive"))
    )
    (net (code "58") (name "unconnected-(U30-9.SWCLK-Pad9)") (class "Default")
      (node (ref "U30") (pin "9") (pinfunction "9.SWCLK_9") (pintype "passive"))
    )
    (net (code "59") (name "unconnected-(U30-10.SWDIO-Pad10)") (class "Default")
      (node (ref "U30") (pin "10") (pinfunction "10.SWDIO_10") (pintype "passive"))
    )
    (net (code "60") (name "unconnected-(U30-11.PIO3-Pad11)") (class "Default")
      (node (ref "U30") (pin "11") (pinfunction "11.PIO3_11") (pintype "passive"))
    )
    (net (code "61") (name "unconnected-(U30-12.PIO4-Pad12)") (class "Default")
      (node (ref "U30") (pin "12") (pinfunction "12.PIO4_12") (pintype "passive"))
    )
    (net (code "62") (name "unconnected-(U30-13.PIO5-Pad13)") (class "Default")
      (node (ref "U30") (pin "13") (pinfunction "13.PIO5_13") (pintype "passive"))
    )
    (net (code "63") (name "unconnected-(U30-14.PIO6-Pad14)") (class "Default")
      (node (ref "U30") (pin "14") (pinfunction "14.PIO6_14") (pintype "passive"))
    )
    (net (code "64") (name "unconnected-(U30-15.PIO7-Pad15)") (class "Default")
      (node (ref "U30") (pin "15") (pinfunction "15.PIO7_15") (pintype "passive"))
    )
    (net (code "65") (name "unconnected-(U30-16.PIO8-Pad16)") (class "Default")
      (node (ref "U30") (pin "16") (pinfunction "16.PIO8_16") (pintype "passive"))
    )
    (net (code "66") (name "unconnected-(U30-17.LED-Pad17)") (class "Default")
      (node (ref "U30") (pin "17") (pinfunction "17.LED_17") (pintype "passive"))
    )
    (net (code "67") (name "unconnected-(U30-20.EXT_ANT-Pad20)") (class "Default")
      (node (ref "U30") (pin "20") (pinfunction "20.EXT_ANT_20") (pintype "passive"))
    )
    (net (code "68") (name "~{BLE_RESET}") (class "Default")
      (node (ref "U10") (pin "25") (pinfunction "25.PB12_25") (pintype "passive"))
      (node (ref "U30") (pin "6") (pinfunction "6.~{RESET}_6") (pintype "passive"))
    )
    (net (code "69") (name "~{RST}") (class "Default")
      (node (ref "C10R") (pin "1") (pinfunction "1_1") (pintype "passive"))
      (node (ref "SW10R") (pin "1") (pinfunction "1-2_1") (pintype "passive"))
      (node (ref "U10") (pin "7") (pinfunction "7.~{RST}_7") (pintype "passive"))
    )
    (net (code "70") (name "~{SENSOR_PWR}") (class "Default")
      (node (ref "R40P") (pin "2") (pinfunction "2_2") (pintype "passive"))
      (node (ref "T40P") (pin "1") (pinfunction "G_1") (pintype "bidirectional"))
      (node (ref "U10") (pin "46") (pinfunction "46.PB9_46") (pintype "passive"))
    )
  )
)
